# BT612-4-V1_0.net
KiCad netlist of a schematic drawn in Altium Designer
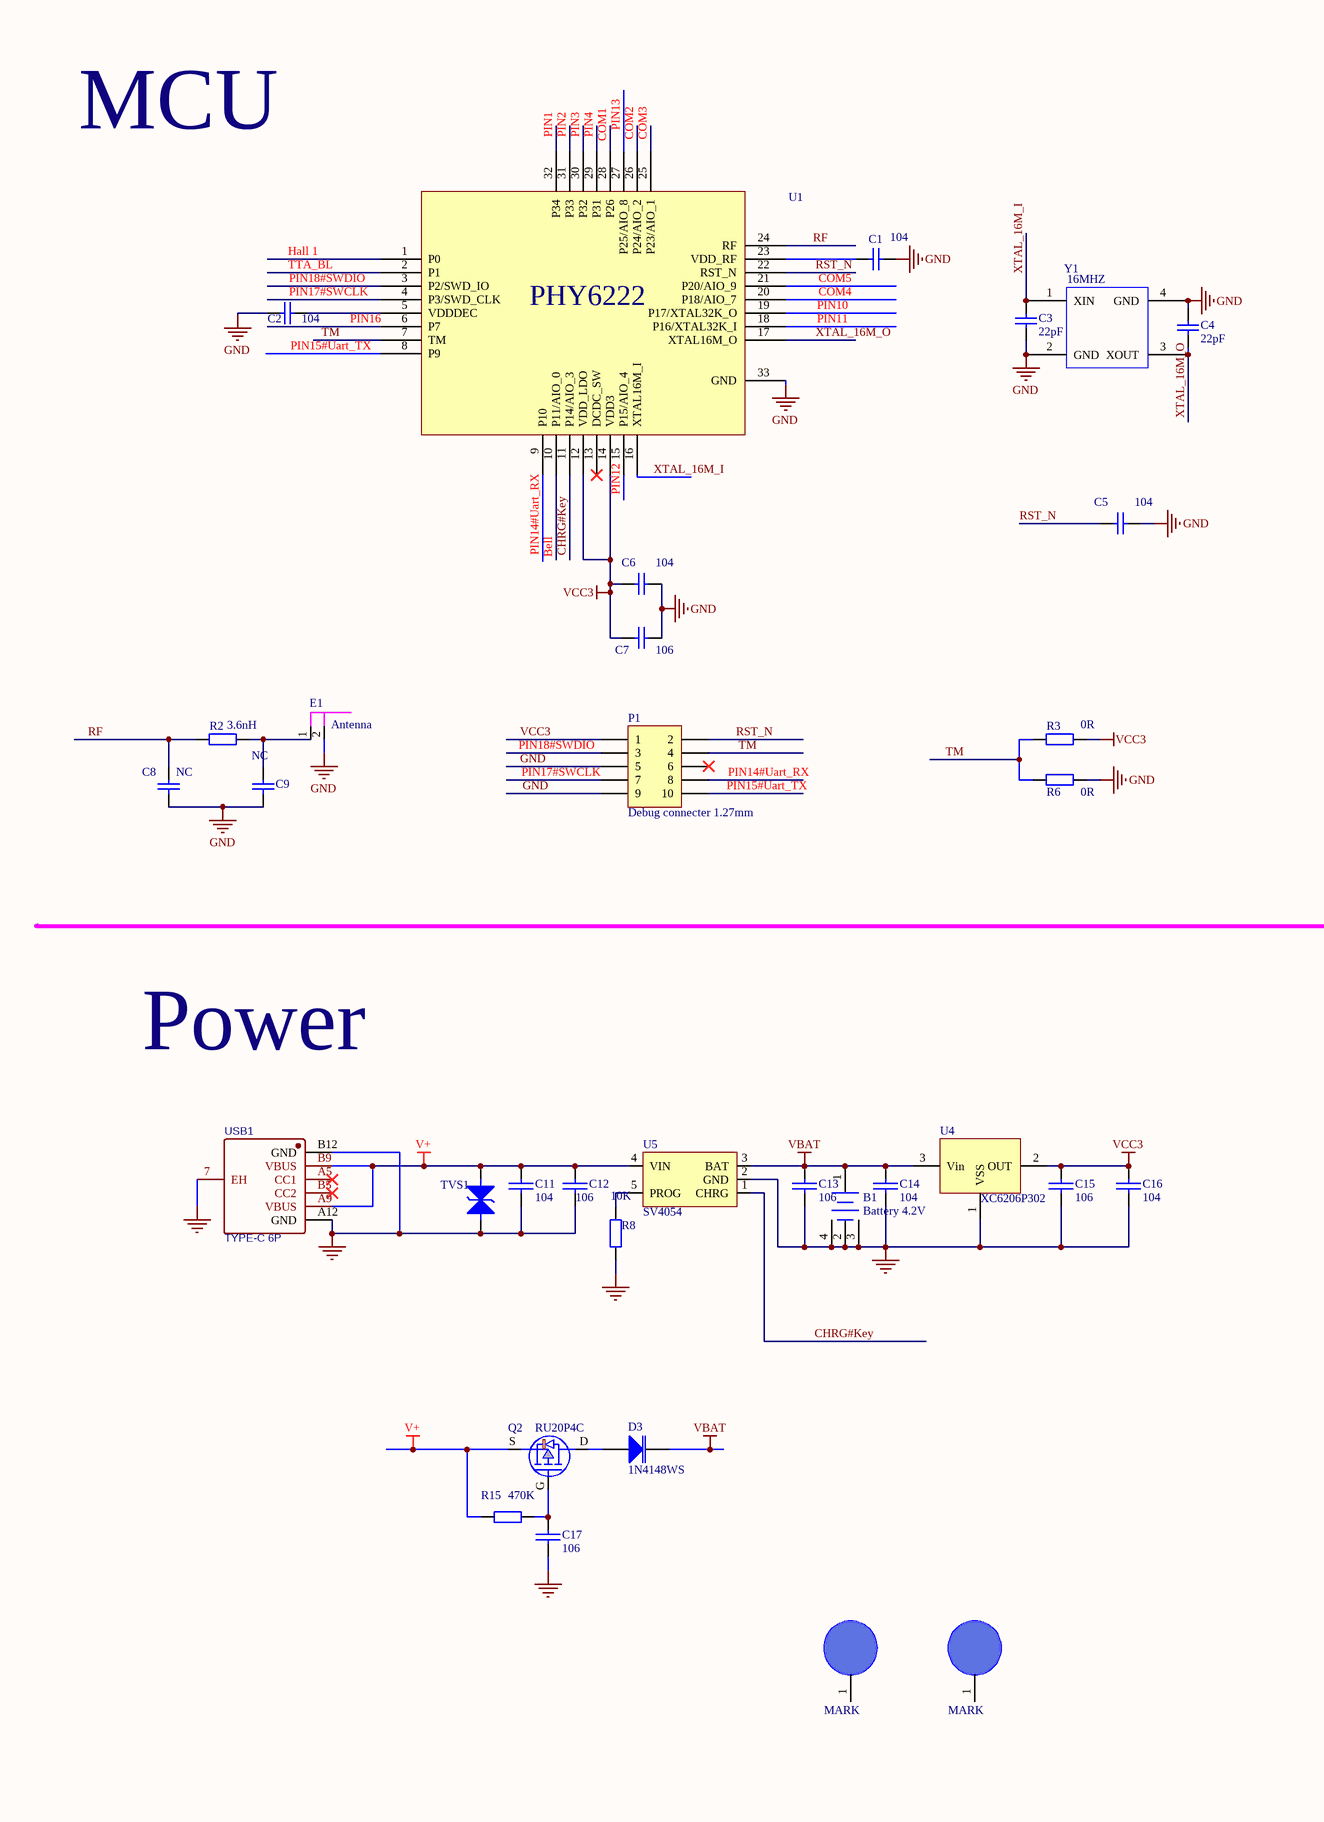
[diagram p0: BT612-4-V1.0.SchDoc, left]
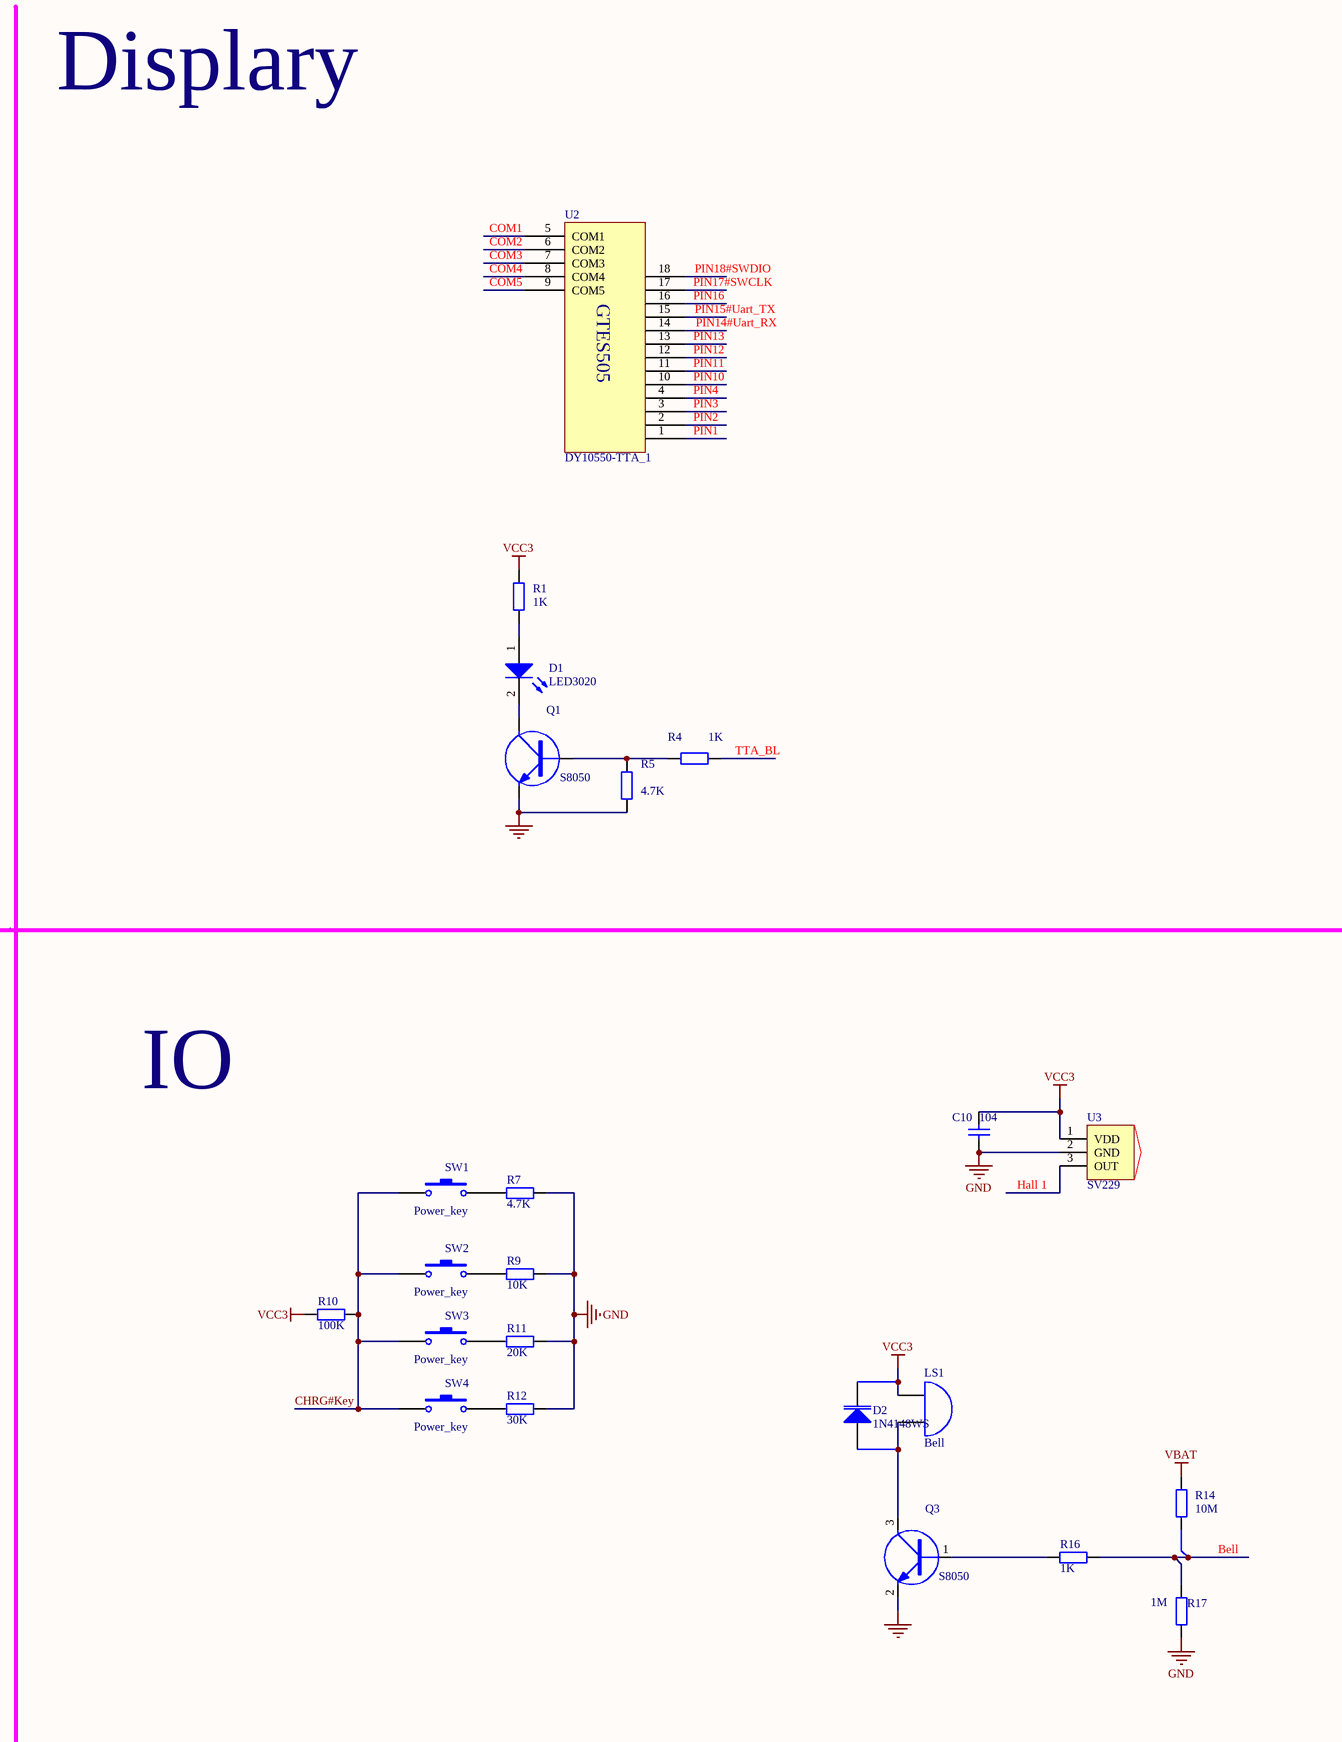
[diagram p1: BT612-4-V1.0.SchDoc, right]

(export (version "E")
  (design (tool "Eeschema 10.0.6"))
  (components
    (comp (ref "B1")
      (value "Battery 4.2V")
      (footprint "BAT2P-1.25")
      (description "Multicell Battery")
      (fields (field (name "PUBLISHER") "Altium Limited"))
      (libsource (lib "SR4K_PHY6222_simplify_v1") (part "Battery"))
    )
    (comp (ref "C1")
      (value "104")
      (footprint "0402C")
      (description "Capacitor")
      (fields (field (name "PUBLISHER") "Altium Limited"))
      (libsource (lib "Miscellaneous Devices") (part "Cap"))
    )
    (comp (ref "C2")
      (value "104")
      (footprint "0402C")
      (description "Capacitor")
      (fields (field (name "PUBLISHER") "Altium Limited"))
      (libsource (lib "Miscellaneous Devices") (part "Cap"))
    )
    (comp (ref "C3")
      (value "22pF")
      (footprint "0402C")
      (description "Capacitor")
      (fields (field (name "PUBLISHER") "Altium Limited"))
      (libsource (lib "Miscellaneous Devices") (part "Cap"))
    )
    (comp (ref "C4")
      (value "22pF")
      (footprint "0402C")
      (description "Capacitor")
      (libsource (lib "Miscellaneous Devices") (part "Cap"))
    )
    (comp (ref "C5")
      (value "104")
      (footprint "0402C")
      (description "Capacitor")
      (fields (field (name "PUBLISHER") "Altium Limited"))
      (libsource (lib "Miscellaneous Devices") (part "Cap"))
    )
    (comp (ref "C6")
      (value "104")
      (footprint "0402C")
      (description "Capacitor")
      (fields (field (name "PUBLISHER") "Altium Limited"))
      (libsource (lib "Miscellaneous Devices") (part "Cap"))
    )
    (comp (ref "C7")
      (value "106")
      (footprint "0603-C")
      (description "Capacitor")
      (fields (field (name "PUBLISHER") "Altium Limited"))
      (libsource (lib "Miscellaneous Devices") (part "Cap"))
    )
    (comp (ref "C8")
      (value "NC")
      (footprint "0402C")
      (description "Capacitor")
      (fields (field (name "PUBLISHER") "Altium Limited"))
      (libsource (lib "Miscellaneous Devices") (part "Cap"))
    )
    (comp (ref "C9")
      (value "NC")
      (footprint "0402C")
      (description "Capacitor")
      (fields (field (name "PUBLISHER") "Altium Limited"))
      (libsource (lib "Miscellaneous Devices") (part "Cap"))
    )
    (comp (ref "C10")
      (value "104")
      (footprint "0402C")
      (description "Capacitor")
      (fields (field (name "PUBLISHER") "Altium Limited"))
      (libsource (lib "Miscellaneous Devices") (part "Cap"))
    )
    (comp (ref "C11")
      (value "104")
      (footprint "0402C")
      (description "Capacitor")
      (libsource (lib "*") (part "CAP"))
    )
    (comp (ref "C12")
      (value "106")
      (footprint "0603-C")
      (description "Capacitor")
      (libsource (lib "*") (part "CAP"))
    )
    (comp (ref "C13")
      (value "106")
      (footprint "0603-C")
      (description "Capacitor")
      (libsource (lib "*") (part "CAP"))
    )
    (comp (ref "C14")
      (value "104")
      (footprint "0402C")
      (description "Capacitor")
      (libsource (lib "*") (part "CAP"))
    )
    (comp (ref "C15")
      (value "106")
      (footprint "0603-C")
      (description "Capacitor")
      (libsource (lib "*") (part "CAP"))
    )
    (comp (ref "C16")
      (value "104")
      (footprint "0402C")
      (description "Capacitor")
      (libsource (lib "*") (part "CAP"))
    )
    (comp (ref "C17")
      (value "106")
      (footprint "0603-C")
      (description "Capacitor")
      (libsource (lib "*") (part "CAP"))
    )
    (comp (ref "D1")
      (value "LED3020")
      (footprint "LED-3020")
      (description "Typical INFRARED GaAs LED")
      (fields (field (name "PUBLISHER") "Altium Limited"))
      (libsource (lib "Miscellaneous Devices") (part "LED0"))
    )
    (comp (ref "D2")
      (value "1N4148WS")
      (footprint "SOD323")
      (description "Variable Capacitance Diode")
      (fields (field (name "PUBLISHER") "Altium Limited"))
      (libsource (lib "Miscellaneous Devices") (part "D Varactor"))
    )
    (comp (ref "D3")
      (value "1N4148WS")
      (footprint "SOD323")
      (description "Variable Capacitance Diode")
      (fields (field (name "PUBLISHER") "Altium Limited"))
      (libsource (lib "Miscellaneous Devices") (part "D Varactor"))
    )
    (comp (ref "E1") (value "Antenna") (footprint "BT-ANT") (libsource (lib "Schlib") (part "Antenna")))
    (comp (ref "LS1")
      (value "Bell")
      (footprint "BUZZ-12085")
      (description "Electrical Bell")
      (fields (field (name "PUBLISHER") "Altium Limited"))
      (libsource (lib "Miscellaneous Devices") (part "Bell"))
    )
    (comp (ref "P1")
      (value "Debug connecter 1.27mm")
      (footprint "SIP5-X2-1.27")
      (description "Header, 5-Pin, Dual row")
      (fields (field (name "PUBLISHER") "Altium Limited"))
      (libsource (lib "Miscellaneous Connectors") (part "Header 5X2"))
    )
    (comp (ref "Q1")
      (value "S8050")
      (footprint "SOT23")
      (description "NPN Transistor")
      (libsource (lib "") (part "NPN_1"))
    )
    (comp (ref "Q2") (value "RU20P4C") (footprint "SOT-23-GSD") (libsource (lib "*") (part "P-MOS")))
    (comp (ref "Q3")
      (value "S8050")
      (footprint "SOT23")
      (description "NPN Transistor")
      (libsource (lib "*") (part "NPN"))
    )
    (comp (ref "R1")
      (value "1K")
      (footprint "0402R")
      (description "Resistor")
      (fields (field (name "PUBLISHER") "Altium Limited"))
      (libsource (lib "") (part "Res2_2"))
    )
    (comp (ref "R2")
      (value "3.6nH")
      (footprint "0402R")
      (description "Resistor")
      (fields (field (name "PUBLISHER") "Altium Limited"))
      (libsource (lib "") (part "Res2_1"))
    )
    (comp (ref "R3")
      (value "0R")
      (footprint "0402R")
      (description "Resistor")
      (fields (field (name "PUBLISHER") "Altium Limited"))
      (libsource (lib "") (part "Res2_1"))
    )
    (comp (ref "R4")
      (value "1K")
      (footprint "0402R")
      (description "Resistor")
      (fields (field (name "PUBLISHER") "Altium Limited"))
      (libsource (lib "Miscellaneous Devices") (part "Res2"))
    )
    (comp (ref "R5")
      (value "4.7K")
      (footprint "0402R")
      (description "Resistor")
      (fields (field (name "PUBLISHER") "Altium Limited"))
      (libsource (lib "") (part "Res2_2"))
    )
    (comp (ref "R6")
      (value "0R")
      (footprint "0402R")
      (description "Resistor")
      (fields (field (name "PUBLISHER") "Altium Limited"))
      (libsource (lib "") (part "Res2_1"))
    )
    (comp (ref "R7")
      (value "4.7K")
      (footprint "0402R")
      (description "Resistor")
      (fields (field (name "PUBLISHER") "Altium Limited"))
      (libsource (lib "Miscellaneous Devices") (part "Res2"))
    )
    (comp (ref "R8")
      (value "10K")
      (footprint "0402R")
      (description "1%@100mA")
      (fields (field (name "PUBLISHER") "Altium Limited"))
      (libsource (lib "") (part "Res2_2"))
    )
    (comp (ref "R9")
      (value "10K")
      (footprint "0402R")
      (description "Resistor")
      (fields (field (name "PUBLISHER") "Altium Limited"))
      (libsource (lib "Miscellaneous Devices") (part "Res2"))
    )
    (comp (ref "R10")
      (value "100K")
      (footprint "0402R")
      (description "Resistor")
      (fields (field (name "PUBLISHER") "Altium Limited"))
      (libsource (lib "Miscellaneous Devices") (part "Res2"))
    )
    (comp (ref "R11")
      (value "20K")
      (footprint "0402R")
      (description "Resistor")
      (fields (field (name "PUBLISHER") "Altium Limited"))
      (libsource (lib "Miscellaneous Devices") (part "Res2"))
    )
    (comp (ref "R12")
      (value "30K")
      (footprint "0402R")
      (description "Resistor")
      (fields (field (name "PUBLISHER") "Altium Limited"))
      (libsource (lib "Miscellaneous Devices") (part "Res2"))
    )
    (comp (ref "R14")
      (value "10M")
      (footprint "0402R")
      (description "Resistor")
      (fields (field (name "PUBLISHER") "Altium Limited"))
      (libsource (lib "") (part "Res2_2"))
    )
    (comp (ref "R15")
      (value "470K")
      (footprint "0402R")
      (description "1%@100mA")
      (fields (field (name "PUBLISHER") "Altium Limited"))
      (libsource (lib "") (part "Res2_1"))
    )
    (comp (ref "R16")
      (value "1K")
      (footprint "0402R")
      (description "Resistor")
      (fields (field (name "PUBLISHER") "Altium Limited"))
      (libsource (lib "Miscellaneous Devices") (part "Res2"))
    )
    (comp (ref "R17")
      (value "1M")
      (footprint "0402R")
      (description "Resistor")
      (fields (field (name "PUBLISHER") "Altium Limited"))
      (libsource (lib "") (part "Res2_2"))
    )
    (comp (ref "SW1")
      (value "Power_key")
      (footprint "SW_PB_SMD_4X4")
      (description "Switch")
      (fields (field (name "PUBLISHER") "Altium Limited"))
      (libsource (lib "Miscellaneous Devices") (part "SW-PB"))
    )
    (comp (ref "SW2")
      (value "Power_key")
      (footprint "SW_PB_SMD_4X4")
      (description "Switch")
      (fields (field (name "PUBLISHER") "Altium Limited"))
      (libsource (lib "Miscellaneous Devices") (part "SW-PB"))
    )
    (comp (ref "SW3")
      (value "Power_key")
      (footprint "SW_PB_SMD_4X4")
      (description "Switch")
      (fields (field (name "PUBLISHER") "Altium Limited"))
      (libsource (lib "Miscellaneous Devices") (part "SW-PB"))
    )
    (comp (ref "SW4")
      (value "Power_key")
      (footprint "SW_PB_SMD_4X4")
      (description "Switch")
      (fields (field (name "PUBLISHER") "Altium Limited"))
      (libsource (lib "Miscellaneous Devices") (part "SW-PB"))
    )
    (comp (ref "TP1") (value "MARK") (footprint "MARK") (libsource (lib "BT612-4") (part "TP")))
    (comp (ref "TP2") (value "MARK") (footprint "MARK") (libsource (lib "BT612-4") (part "TP")))
    (comp (ref "TVS1") (value "TVS") (footprint "SOD323") (libsource (lib "*") (part "TVS")))
    (comp (ref "U1")
      (value "PHY6222")
      (footprint "QFN32-4*4")
      (libsource (lib "SR4K_PHY6222_simplify_v1") (part "PHY6222"))
    )
    (comp (ref "U2")
      (value "DY10550-TTA_1")
      (footprint "GTES505液晶屏")
      (libsource (lib "BT612-4") (part "DY10550-TTA_1"))
    )
    (comp (ref "U3") (value "SV229") (footprint "SOT23-3") (libsource (lib "*") (part "霍尔44E 938")))
    (comp (ref "U4") (value "XC6206P302") (footprint "SOT23") (libsource (lib "*") (part "XC6206P302")))
    (comp (ref "U5") (value "SV4054") (footprint "SOT23-5") (libsource (lib "*") (part "SV4054")))
    (comp (ref "USB1")
      (value "TYPE-C 6P")
      (footprint "TYPE-C 6P")
      (fields (field (name "BOM_SUPPLIER PART") "C456012") (field (name "CONTRIBUTOR") "LCSC"))
      (libsource (lib "altium-import") (part "root_0_mirrored_TYPE-C 6P_"))
    )
    (comp (ref "Y1") (value "16MHZ") (footprint "JZ-3225") (libsource (lib "*") (part "X1_1")))
  )
  (nets
    (net (code "1") (name "/Bell") (class "Default")
      (node (ref "R14") (pin "1") (pinfunction "1_1") (pintype "passive"))
      (node (ref "R16") (pin "2") (pinfunction "2_2") (pintype "passive"))
      (node (ref "R17") (pin "2") (pinfunction "2_2") (pintype "passive"))
      (node (ref "U1") (pin "10") (pinfunction "P11/AIO_0_10") (pintype "passive"))
    )
    (net (code "2") (name "/CHRG#Key") (class "Default")
      (node (ref "R10") (pin "2") (pinfunction "2_2") (pintype "passive"))
      (node (ref "SW1") (pin "1") (pinfunction "1_1") (pintype "passive"))
      (node (ref "SW2") (pin "1") (pinfunction "1_1") (pintype "passive"))
      (node (ref "SW3") (pin "1") (pinfunction "1_1") (pintype "passive"))
      (node (ref "SW4") (pin "1") (pinfunction "1_1") (pintype "passive"))
      (node (ref "U1") (pin "11") (pinfunction "P14/AIO_3_11") (pintype "passive"))
      (node (ref "U5") (pin "1") (pinfunction "CHRG_1") (pintype "passive"))
    )
    (net (code "3") (name "/COM1") (class "Default")
      (node (ref "U1") (pin "28") (pinfunction "P26_28") (pintype "passive"))
      (node (ref "U2") (pin "5") (pinfunction "COM1_5") (pintype "passive"))
    )
    (net (code "4") (name "/COM2") (class "Default")
      (node (ref "U1") (pin "26") (pinfunction "P24/AIO_2_26") (pintype "passive"))
      (node (ref "U2") (pin "6") (pinfunction "COM2_6") (pintype "passive"))
    )
    (net (code "5") (name "/COM3") (class "Default")
      (node (ref "U1") (pin "25") (pinfunction "P23/AIO_1_25") (pintype "passive"))
      (node (ref "U2") (pin "7") (pinfunction "COM3_7") (pintype "passive"))
    )
    (net (code "6") (name "/COM4") (class "Default")
      (node (ref "U1") (pin "20") (pinfunction "P18/AIO_7_20") (pintype "passive"))
      (node (ref "U2") (pin "8") (pinfunction "COM4_8") (pintype "passive"))
    )
    (net (code "7") (name "/COM5") (class "Default")
      (node (ref "U1") (pin "21") (pinfunction "P20/AIO_9_21") (pintype "passive"))
      (node (ref "U2") (pin "9") (pinfunction "COM5_9") (pintype "passive"))
    )
    (net (code "8") (name "/Hall 1") (class "Default")
      (node (ref "U1") (pin "1") (pinfunction "P0_1") (pintype "passive"))
      (node (ref "U3") (pin "3") (pinfunction "OUT_3") (pintype "passive"))
    )
    (net (code "9") (name "/PIN1") (class "Default")
      (node (ref "U1") (pin "32") (pinfunction "P34_32") (pintype "passive"))
      (node (ref "U2") (pin "1") (pintype "passive"))
    )
    (net (code "10") (name "/PIN2") (class "Default")
      (node (ref "U1") (pin "31") (pinfunction "P33_31") (pintype "passive"))
      (node (ref "U2") (pin "2") (pintype "passive"))
    )
    (net (code "11") (name "/PIN3") (class "Default")
      (node (ref "U1") (pin "30") (pinfunction "P32_30") (pintype "passive"))
      (node (ref "U2") (pin "3") (pintype "passive"))
    )
    (net (code "12") (name "/PIN4") (class "Default")
      (node (ref "U1") (pin "29") (pinfunction "P31_29") (pintype "passive"))
      (node (ref "U2") (pin "4") (pintype "passive"))
    )
    (net (code "13") (name "/PIN10") (class "Default")
      (node (ref "U1") (pin "19") (pinfunction "P17/XTAL32K_O_19") (pintype "passive"))
      (node (ref "U2") (pin "10") (pintype "passive"))
    )
    (net (code "14") (name "/PIN11") (class "Default")
      (node (ref "U1") (pin "18") (pinfunction "P16/XTAL32K_I_18") (pintype "passive"))
      (node (ref "U2") (pin "11") (pintype "passive"))
    )
    (net (code "15") (name "/PIN12") (class "Default")
      (node (ref "U1") (pin "15") (pinfunction "P15/AIO_4_15") (pintype "passive"))
      (node (ref "U2") (pin "12") (pintype "passive"))
    )
    (net (code "16") (name "/PIN13") (class "Default")
      (node (ref "U1") (pin "27") (pinfunction "P25/AIO_8_27") (pintype "passive"))
      (node (ref "U2") (pin "13") (pintype "passive"))
    )
    (net (code "17") (name "/PIN14#Uart_RX") (class "Default")
      (node (ref "P1") (pin "8") (pinfunction "8_8") (pintype "passive"))
      (node (ref "U1") (pin "9") (pinfunction "P10_9") (pintype "passive"))
      (node (ref "U2") (pin "14") (pintype "passive"))
    )
    (net (code "18") (name "/PIN15#Uart_TX") (class "Default")
      (node (ref "P1") (pin "10") (pinfunction "10_10") (pintype "passive"))
      (node (ref "U1") (pin "8") (pinfunction "P9_8") (pintype "passive"))
      (node (ref "U2") (pin "15") (pintype "passive"))
    )
    (net (code "19") (name "/PIN16") (class "Default")
      (node (ref "U1") (pin "6") (pinfunction "P7_6") (pintype "passive"))
      (node (ref "U2") (pin "16") (pintype "passive"))
    )
    (net (code "20") (name "/PIN17#SWCLK") (class "Default")
      (node (ref "P1") (pin "7") (pinfunction "7_7") (pintype "passive"))
      (node (ref "U1") (pin "4") (pinfunction "P3/SWD_CLK_4") (pintype "passive"))
      (node (ref "U2") (pin "17") (pintype "passive"))
    )
    (net (code "21") (name "/PIN18#SWDIO") (class "Default")
      (node (ref "P1") (pin "3") (pinfunction "3_3") (pintype "passive"))
      (node (ref "U1") (pin "3") (pinfunction "P2/SWD_IO_3") (pintype "passive"))
      (node (ref "U2") (pin "18") (pintype "passive"))
    )
    (net (code "22") (name "/RF") (class "Default")
      (node (ref "C8") (pin "1") (pinfunction "1_1") (pintype "passive"))
      (node (ref "R2") (pin "2") (pinfunction "2_2") (pintype "passive"))
      (node (ref "U1") (pin "24") (pinfunction "RF_24") (pintype "passive"))
    )
    (net (code "23") (name "/RST_N") (class "Default")
      (node (ref "C5") (pin "1") (pinfunction "1_1") (pintype "passive"))
      (node (ref "P1") (pin "2") (pinfunction "2_2") (pintype "passive"))
      (node (ref "U1") (pin "22") (pinfunction "RST_N_22") (pintype "passive"))
    )
    (net (code "24") (name "/TM") (class "Default")
      (node (ref "P1") (pin "4") (pinfunction "4_4") (pintype "passive"))
      (node (ref "R3") (pin "2") (pinfunction "2_2") (pintype "passive"))
      (node (ref "R6") (pin "2") (pinfunction "2_2") (pintype "passive"))
      (node (ref "U1") (pin "7") (pinfunction "TM_7") (pintype "passive"))
    )
    (net (code "25") (name "/TTA_BL") (class "Default")
      (node (ref "R4") (pin "2") (pinfunction "2_2") (pintype "passive"))
      (node (ref "U1") (pin "2") (pinfunction "P1_2") (pintype "passive"))
    )
    (net (code "26") (name "/XTAL_16M_I") (class "Default")
      (node (ref "C3") (pin "1") (pinfunction "1_1") (pintype "passive"))
      (node (ref "U1") (pin "16") (pinfunction "XTAL16M_I_16") (pintype "passive"))
      (node (ref "Y1") (pin "1") (pinfunction "XIN_1") (pintype "passive"))
    )
    (net (code "27") (name "/XTAL_16M_O") (class "Default")
      (node (ref "C4") (pin "2") (pinfunction "2_2") (pintype "passive"))
      (node (ref "U1") (pin "17") (pinfunction "XTAL16M_O_17") (pintype "passive"))
      (node (ref "Y1") (pin "3") (pinfunction "XOUT_3") (pintype "passive"))
    )
    (net (code "28") (name "GND") (class "Default")
      (node (ref "B1") (pin "2") (pinfunction "-_2") (pintype "passive"))
      (node (ref "B1") (pin "3") (pinfunction "3_3") (pintype "passive"))
      (node (ref "B1") (pin "4") (pinfunction "4_4") (pintype "passive"))
      (node (ref "C1") (pin "2") (pinfunction "2_2") (pintype "passive"))
      (node (ref "C10") (pin "2") (pinfunction "2_2") (pintype "passive"))
      (node (ref "C11") (pin "1") (pinfunction "1_1") (pintype "passive"))
      (node (ref "C12") (pin "1") (pinfunction "1_1") (pintype "passive"))
      (node (ref "C13") (pin "1") (pinfunction "1_1") (pintype "passive"))
      (node (ref "C14") (pin "1") (pinfunction "1_1") (pintype "passive"))
      (node (ref "C15") (pin "1") (pinfunction "1_1") (pintype "passive"))
      (node (ref "C16") (pin "1") (pinfunction "1_1") (pintype "passive"))
      (node (ref "C17") (pin "1") (pinfunction "1_1") (pintype "passive"))
      (node (ref "C2") (pin "1") (pinfunction "1_1") (pintype "passive"))
      (node (ref "C3") (pin "2") (pinfunction "2_2") (pintype "passive"))
      (node (ref "C4") (pin "1") (pinfunction "1_1") (pintype "passive"))
      (node (ref "C5") (pin "2") (pinfunction "2_2") (pintype "passive"))
      (node (ref "C6") (pin "2") (pinfunction "2_2") (pintype "passive"))
      (node (ref "C7") (pin "2") (pinfunction "2_2") (pintype "passive"))
      (node (ref "C8") (pin "2") (pinfunction "2_2") (pintype "passive"))
      (node (ref "C9") (pin "2") (pinfunction "2_2") (pintype "passive"))
      (node (ref "E1") (pin "2") (pinfunction "2_2") (pintype "passive"))
      (node (ref "P1") (pin "5") (pinfunction "5_5") (pintype "passive"))
      (node (ref "P1") (pin "9") (pinfunction "9_9") (pintype "passive"))
      (node (ref "Q1") (pin "2") (pinfunction "E_2") (pintype "passive"))
      (node (ref "Q3") (pin "2") (pinfunction "E_2") (pintype "passive"))
      (node (ref "R11") (pin "2") (pinfunction "2_2") (pintype "passive"))
      (node (ref "R12") (pin "2") (pinfunction "2_2") (pintype "passive"))
      (node (ref "R17") (pin "1") (pinfunction "1_1") (pintype "passive"))
      (node (ref "R5") (pin "1") (pinfunction "1_1") (pintype "passive"))
      (node (ref "R6") (pin "1") (pinfunction "1_1") (pintype "passive"))
      (node (ref "R7") (pin "2") (pinfunction "2_2") (pintype "passive"))
      (node (ref "R8") (pin "1") (pinfunction "1_1") (pintype "passive"))
      (node (ref "R9") (pin "2") (pinfunction "2_2") (pintype "passive"))
      (node (ref "TVS1") (pin "1") (pinfunction "1_1") (pintype "passive"))
      (node (ref "U1") (pin "33") (pinfunction "GND_33") (pintype "power_in"))
      (node (ref "U3") (pin "2") (pinfunction "GND_2") (pintype "passive"))
      (node (ref "U4") (pin "1") (pinfunction "VSS_1") (pintype "passive"))
      (node (ref "U5") (pin "2") (pinfunction "GND_2") (pintype "passive"))
      (node (ref "USB1") (pin "7") (pinfunction "EH_7") (pintype "passive"))
      (node (ref "USB1") (pin "A12") (pinfunction "GND_A12") (pintype "passive"))
      (node (ref "USB1") (pin "B12") (pinfunction "GND_B12") (pintype "passive"))
      (node (ref "Y1") (pin "2") (pinfunction "GND_2") (pintype "power_in"))
      (node (ref "Y1") (pin "4") (pinfunction "GND_4") (pintype "power_in"))
    )
    (net (code "29") (name "Net-(C9-Pad1)") (class "Default")
      (node (ref "C9") (pin "1") (pinfunction "1_1") (pintype "passive"))
      (node (ref "E1") (pin "1") (pinfunction "1_1") (pintype "passive"))
      (node (ref "R2") (pin "1") (pinfunction "1_1") (pintype "passive"))
    )
    (net (code "30") (name "Net-(D1-A)") (class "Default")
      (node (ref "D1") (pin "1") (pinfunction "A_1") (pintype "passive"))
      (node (ref "R1") (pin "1") (pinfunction "1_1") (pintype "passive"))
    )
    (net (code "31") (name "Net-(D1-K)") (class "Default")
      (node (ref "D1") (pin "2") (pinfunction "K_2") (pintype "passive"))
      (node (ref "Q1") (pin "3") (pinfunction "C_3") (pintype "passive"))
    )
    (net (code "32") (name "Net-(LS1-B)") (class "Default")
      (node (ref "D2") (pin "1") (pinfunction "1_1") (pintype "passive"))
      (node (ref "LS1") (pin "2") (pinfunction "B_2") (pintype "passive"))
      (node (ref "Q3") (pin "3") (pinfunction "C_3") (pintype "passive"))
    )
    (net (code "33") (name "Net-(Q1-B)") (class "Default")
      (node (ref "Q1") (pin "1") (pinfunction "B_1") (pintype "passive"))
      (node (ref "R4") (pin "1") (pinfunction "1_1") (pintype "passive"))
      (node (ref "R5") (pin "2") (pinfunction "2_2") (pintype "passive"))
    )
    (net (code "34") (name "Net-(Q2-DRAIN)") (class "Default")
      (node (ref "D3") (pin "1") (pinfunction "1_1") (pintype "passive"))
      (node (ref "Q2") (pin "D") (pinfunction "DRAIN_D") (pintype "passive"))
    )
    (net (code "35") (name "Net-(Q2-GATE)") (class "Default")
      (node (ref "C17") (pin "2") (pinfunction "2_2") (pintype "passive"))
      (node (ref "Q2") (pin "G") (pinfunction "GATE_G") (pintype "passive"))
      (node (ref "R15") (pin "1") (pinfunction "1_1") (pintype "passive"))
    )
    (net (code "36") (name "Net-(Q3-B)") (class "Default")
      (node (ref "Q3") (pin "1") (pinfunction "B_1") (pintype "passive"))
      (node (ref "R16") (pin "1") (pinfunction "1_1") (pintype "passive"))
    )
    (net (code "37") (name "Net-(R7-Pad1)") (class "Default")
      (node (ref "R7") (pin "1") (pinfunction "1_1") (pintype "passive"))
      (node (ref "SW1") (pin "2") (pinfunction "2_2") (pintype "passive"))
    )
    (net (code "38") (name "Net-(R9-Pad1)") (class "Default")
      (node (ref "R9") (pin "1") (pinfunction "1_1") (pintype "passive"))
      (node (ref "SW2") (pin "2") (pinfunction "2_2") (pintype "passive"))
    )
    (net (code "39") (name "Net-(R11-Pad1)") (class "Default")
      (node (ref "R11") (pin "1") (pinfunction "1_1") (pintype "passive"))
      (node (ref "SW3") (pin "2") (pinfunction "2_2") (pintype "passive"))
    )
    (net (code "40") (name "Net-(R12-Pad1)") (class "Default")
      (node (ref "R12") (pin "1") (pinfunction "1_1") (pintype "passive"))
      (node (ref "SW4") (pin "2") (pinfunction "2_2") (pintype "passive"))
    )
    (net (code "41") (name "Net-(U1-VDDDEC)") (class "Default")
      (node (ref "C2") (pin "2") (pinfunction "2_2") (pintype "passive"))
      (node (ref "U1") (pin "5") (pinfunction "VDDDEC_5") (pintype "power_in"))
    )
    (net (code "42") (name "Net-(U1-VDD_RF)") (class "Default")
      (node (ref "C1") (pin "1") (pinfunction "1_1") (pintype "passive"))
      (node (ref "U1") (pin "23") (pinfunction "VDD_RF_23") (pintype "power_in"))
    )
    (net (code "43") (name "Net-(U5-PROG)") (class "Default")
      (node (ref "R8") (pin "2") (pinfunction "2_2") (pintype "passive"))
      (node (ref "U5") (pin "5") (pinfunction "PROG_5") (pintype "passive"))
    )
    (net (code "44") (name "V+") (class "Default")
      (node (ref "C11") (pin "2") (pinfunction "2_2") (pintype "passive"))
      (node (ref "C12") (pin "2") (pinfunction "2_2") (pintype "passive"))
      (node (ref "Q2") (pin "S") (pinfunction "SOURCE_S") (pintype "passive"))
      (node (ref "R15") (pin "2") (pinfunction "2_2") (pintype "passive"))
      (node (ref "TVS1") (pin "2") (pinfunction "2_2") (pintype "passive"))
      (node (ref "U5") (pin "4") (pinfunction "VIN_4") (pintype "passive"))
      (node (ref "USB1") (pin "A9") (pinfunction "VBUS_A9") (pintype "passive"))
      (node (ref "USB1") (pin "B9") (pinfunction "VBUS_B9") (pintype "passive"))
    )
    (net (code "45") (name "VBAT") (class "Default")
      (node (ref "B1") (pin "1") (pinfunction "+_1") (pintype "passive"))
      (node (ref "C13") (pin "2") (pinfunction "2_2") (pintype "passive"))
      (node (ref "C14") (pin "2") (pinfunction "2_2") (pintype "passive"))
      (node (ref "D3") (pin "2") (pinfunction "2_2") (pintype "passive"))
      (node (ref "R14") (pin "2") (pinfunction "2_2") (pintype "passive"))
      (node (ref "U4") (pin "3") (pinfunction "Vin_3") (pintype "passive"))
      (node (ref "U5") (pin "3") (pinfunction "BAT_3") (pintype "passive"))
    )
    (net (code "46") (name "VCC3") (class "Default")
      (node (ref "C10") (pin "1") (pinfunction "1_1") (pintype "passive"))
      (node (ref "C15") (pin "2") (pinfunction "2_2") (pintype "passive"))
      (node (ref "C16") (pin "2") (pinfunction "2_2") (pintype "passive"))
      (node (ref "C6") (pin "1") (pinfunction "1_1") (pintype "passive"))
      (node (ref "C7") (pin "1") (pinfunction "1_1") (pintype "passive"))
      (node (ref "D2") (pin "2") (pinfunction "2_2") (pintype "passive"))
      (node (ref "LS1") (pin "1") (pinfunction "A_1") (pintype "passive"))
      (node (ref "P1") (pin "1") (pinfunction "1_1") (pintype "passive"))
      (node (ref "R1") (pin "2") (pinfunction "2_2") (pintype "passive"))
      (node (ref "R10") (pin "1") (pinfunction "1_1") (pintype "passive"))
      (node (ref "R3") (pin "1") (pinfunction "1_1") (pintype "passive"))
      (node (ref "U1") (pin "12") (pinfunction "VDD_LDO_12") (pintype "power_in"))
      (node (ref "U1") (pin "14") (pinfunction "VDD3_14") (pintype "power_in"))
      (node (ref "U3") (pin "1") (pinfunction "VDD_1") (pintype "passive"))
      (node (ref "U4") (pin "2") (pinfunction "OUT_2") (pintype "passive"))
    )
    (net (code "47") (name "unconnected-(P1-Pad6)") (class "Default")
      (node (ref "P1") (pin "6") (pinfunction "6_6") (pintype "passive+no_connect"))
    )
    (net (code "48") (name "unconnected-(TP1-Pad1)") (class "Default")
      (node (ref "TP1") (pin "1") (pinfunction "1_1") (pintype "passive"))
    )
    (net (code "49") (name "unconnected-(TP2-Pad1)") (class "Default")
      (node (ref "TP2") (pin "1") (pinfunction "1_1") (pintype "passive"))
    )
    (net (code "50") (name "unconnected-(U1-DCDC_SW-Pad13)") (class "Default")
      (node (ref "U1") (pin "13") (pinfunction "DCDC_SW_13") (pintype "power_in+no_connect"))
    )
    (net (code "51") (name "unconnected-(USB1-CC1-PadA5)") (class "Default")
      (node (ref "USB1") (pin "A5") (pinfunction "CC1_A5") (pintype "passive+no_connect"))
    )
    (net (code "52") (name "unconnected-(USB1-CC2-PadB5)") (class "Default")
      (node (ref "USB1") (pin "B5") (pinfunction "CC2_B5") (pintype "passive+no_connect"))
    )
  )
)
